# design.net
KiCad netlist of a schematic drawn in Altium Designer
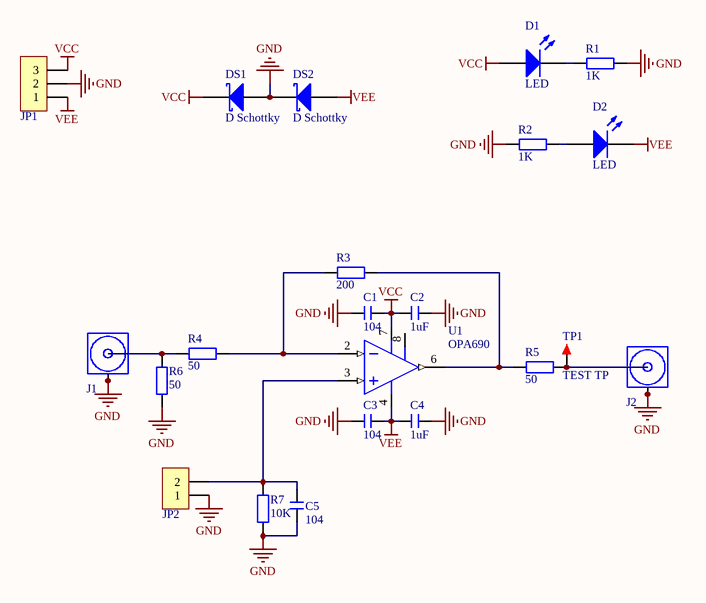
[diagram p0: 调偏电路.SchDoc]

(export (version "E")
  (design (tool "Eeschema 10.0.6"))
  (components
    (comp (ref "C1")
      (value "104")
      (footprint "C 0603")
      (description "无极性贴片电容")
      (fields (field (name "版权归属") "源创客"))
      (libsource (lib "电阻-电容-电感") (part "C"))
    )
    (comp (ref "C2")
      (value "1uF")
      (footprint "C 0603")
      (description "无极性贴片电容")
      (fields (field (name "版权归属") "源创客"))
      (libsource (lib "电阻-电容-电感") (part "C"))
    )
    (comp (ref "C3")
      (value "104")
      (footprint "C 0603")
      (description "无极性贴片电容")
      (fields (field (name "版权归属") "源创客"))
      (libsource (lib "电阻-电容-电感") (part "C"))
    )
    (comp (ref "C4")
      (value "1uF")
      (footprint "C 0603")
      (description "无极性贴片电容")
      (fields (field (name "版权归属") "源创客"))
      (libsource (lib "电阻-电容-电感") (part "C"))
    )
    (comp (ref "C5")
      (value "104")
      (footprint "C 0603")
      (description "无极性贴片电容")
      (fields (field (name "版权归属") "源创客"))
      (libsource (lib "电阻-电容-电感") (part "C"))
    )
    (comp (ref "D1")
      (value "LED")
      (footprint "LED_0805")
      (description "发光二极管")
      (fields (field (name "PUBLISHER") "Altium Limited"))
      (libsource (lib "LIB") (part "LED"))
    )
    (comp (ref "D2")
      (value "LED")
      (footprint "LED_0805")
      (description "发光二极管")
      (fields (field (name "PUBLISHER") "Altium Limited"))
      (libsource (lib "LIB") (part "LED"))
    )
    (comp (ref "DS1")
      (value "D Schottky")
      (footprint "DIODE-SMA")
      (description "Schottky Diode")
      (fields (field (name "PUBLISHER") "Altium Limited"))
      (libsource (lib "LIB") (part "D Schottky"))
    )
    (comp (ref "DS2")
      (value "D Schottky")
      (footprint "DIODE-SMA")
      (description "Schottky Diode")
      (fields (field (name "PUBLISHER") "Altium Limited"))
      (libsource (lib "LIB") (part "D Schottky"))
    )
    (comp (ref "J1") (value "COAX") (footprint "MCX5.08-5-H") (libsource (lib "LIB") (part "COAX")))
    (comp (ref "J2") (value "COAX") (footprint "MCX5.08-5-H") (libsource (lib "LIB") (part "COAX")))
    (comp (ref "JP1")
      (value "HDR-1X3")
      (footprint "XH2.54-3P_H")
      (description "3P接插件")
      (fields (field (name "版权归属") "源创客"))
      (libsource (lib "接插件") (part "Header 3"))
    )
    (comp (ref "JP2")
      (value "HDR-1X2")
      (footprint "HDR-1X2")
      (description "2P接插件")
      (fields (field (name "版权归属") "源创客"))
      (libsource (lib "接插件") (part "Header 2"))
    )
    (comp (ref "R1")
      (value "1K")
      (footprint "R 0805")
      (description "贴片电阻")
      (fields (field (name "版权归属") "源创客"))
      (libsource (lib "电阻-电容-电感") (part "R"))
    )
    (comp (ref "R2")
      (value "1K")
      (footprint "R 0805")
      (description "贴片电阻")
      (fields (field (name "版权归属") "源创客"))
      (libsource (lib "电阻-电容-电感") (part "R"))
    )
    (comp (ref "R3")
      (value "200")
      (footprint "R 0603")
      (description "贴片电阻")
      (fields (field (name "版权归属") "源创客"))
      (libsource (lib "电阻-电容-电感") (part "R"))
    )
    (comp (ref "R4")
      (value "50")
      (footprint "R 0603")
      (description "贴片电阻")
      (fields (field (name "版权归属") "源创客"))
      (libsource (lib "电阻-电容-电感") (part "R"))
    )
    (comp (ref "R5")
      (value "50")
      (footprint "R 0603")
      (description "贴片电阻")
      (fields (field (name "版权归属") "源创客"))
      (libsource (lib "电阻-电容-电感") (part "R"))
    )
    (comp (ref "R6")
      (value "50")
      (footprint "R 0603")
      (description "贴片电阻")
      (fields (field (name "版权归属") "源创客"))
      (libsource (lib "电阻-电容-电感") (part "R"))
    )
    (comp (ref "R7")
      (value "10K")
      (footprint "R 0603")
      (description "贴片电阻")
      (fields (field (name "版权归属") "源创客"))
      (libsource (lib "电阻-电容-电感") (part "R"))
    )
    (comp (ref "TP1")
      (value "TEST TP")
      (footprint "TEST TP1.4_B")
      (description "测试环")
      (fields (field (name "版权归属") "源创客"))
      (libsource (lib "未分类器件") (part "TEST TP"))
    )
    (comp (ref "U1")
      (value "OPA690")
      (footprint "LIB:SOIC8_N")
      (description "具有禁用功能的宽带电压反馈运算放大器")
      (libsource (lib "LIB") (part "OPA690ID"))
    )
  )
  (nets
    (net (code "1") (name "GND") (class "Default")
      (node (ref "C1") (pin "1") (pinfunction "1_1") (pintype "passive"))
      (node (ref "C2") (pin "2") (pinfunction "2_2") (pintype "passive"))
      (node (ref "C3") (pin "1") (pinfunction "1_1") (pintype "passive"))
      (node (ref "C4") (pin "2") (pinfunction "2_2") (pintype "passive"))
      (node (ref "C5") (pin "1") (pinfunction "1_1") (pintype "passive"))
      (node (ref "DS1") (pin "1") (pinfunction "1_1") (pintype "passive"))
      (node (ref "DS2") (pin "2") (pinfunction "2_2") (pintype "passive"))
      (node (ref "J1") (pin "2") (pinfunction "GND_2") (pintype "passive"))
      (node (ref "J1") (pin "3") (pinfunction "GND_3") (pintype "passive"))
      (node (ref "J1") (pin "4") (pinfunction "GND_4") (pintype "passive"))
      (node (ref "J1") (pin "5") (pinfunction "GND_5") (pintype "passive"))
      (node (ref "J2") (pin "2") (pinfunction "GND_2") (pintype "passive"))
      (node (ref "J2") (pin "3") (pinfunction "GND_3") (pintype "passive"))
      (node (ref "J2") (pin "4") (pinfunction "GND_4") (pintype "passive"))
      (node (ref "J2") (pin "5") (pinfunction "GND_5") (pintype "passive"))
      (node (ref "JP1") (pin "2") (pinfunction "2_2") (pintype "passive"))
      (node (ref "JP2") (pin "1") (pinfunction "1_1") (pintype "passive"))
      (node (ref "R1") (pin "2") (pinfunction "2_2") (pintype "passive"))
      (node (ref "R2") (pin "1") (pinfunction "1_1") (pintype "passive"))
      (node (ref "R6") (pin "1") (pinfunction "1_1") (pintype "passive"))
      (node (ref "R7") (pin "1") (pinfunction "1_1") (pintype "passive"))
    )
    (net (code "2") (name "Net-(D1-K)") (class "Default")
      (node (ref "D1") (pin "2") (pinfunction "K_2") (pintype "passive"))
      (node (ref "R1") (pin "1") (pinfunction "1_1") (pintype "passive"))
    )
    (net (code "3") (name "Net-(D2-A)") (class "Default")
      (node (ref "D2") (pin "1") (pinfunction "A_1") (pintype "passive"))
      (node (ref "R2") (pin "2") (pinfunction "2_2") (pintype "passive"))
    )
    (net (code "4") (name "Net-(J1-Signal)") (class "Default")
      (node (ref "J1") (pin "1") (pinfunction "Signal_1") (pintype "passive"))
      (node (ref "R4") (pin "1") (pinfunction "1_1") (pintype "passive"))
      (node (ref "R6") (pin "2") (pinfunction "2_2") (pintype "passive"))
    )
    (net (code "5") (name "Net-(J2-Signal)") (class "Default")
      (node (ref "J2") (pin "1") (pinfunction "Signal_1") (pintype "passive"))
      (node (ref "R5") (pin "2") (pinfunction "2_2") (pintype "passive"))
      (node (ref "TP1") (pin "1") (pinfunction "1_1") (pintype "passive"))
    )
    (net (code "6") (name "Net-(U1-IN+)") (class "Default")
      (node (ref "C5") (pin "2") (pinfunction "2_2") (pintype "passive"))
      (node (ref "JP2") (pin "2") (pinfunction "2_2") (pintype "passive"))
      (node (ref "R7") (pin "2") (pinfunction "2_2") (pintype "passive"))
      (node (ref "U1") (pin "3") (pinfunction "IN+_3") (pintype "input"))
    )
    (net (code "7") (name "Net-(U1-IN-)") (class "Default")
      (node (ref "R3") (pin "1") (pinfunction "1_1") (pintype "passive"))
      (node (ref "R4") (pin "2") (pinfunction "2_2") (pintype "passive"))
      (node (ref "U1") (pin "2") (pinfunction "IN-_2") (pintype "input"))
    )
    (net (code "8") (name "Net-(U1-OUT)") (class "Default")
      (node (ref "R3") (pin "2") (pinfunction "2_2") (pintype "passive"))
      (node (ref "R5") (pin "1") (pinfunction "1_1") (pintype "passive"))
      (node (ref "U1") (pin "6") (pinfunction "OUT_6") (pintype "output"))
    )
    (net (code "9") (name "VCC") (class "Default")
      (node (ref "C1") (pin "2") (pinfunction "2_2") (pintype "passive"))
      (node (ref "C2") (pin "1") (pinfunction "1_1") (pintype "passive"))
      (node (ref "D1") (pin "1") (pinfunction "A_1") (pintype "passive"))
      (node (ref "DS1") (pin "2") (pinfunction "2_2") (pintype "passive"))
      (node (ref "JP1") (pin "3") (pinfunction "3_3") (pintype "passive"))
      (node (ref "U1") (pin "7") (pinfunction "V+_7") (pintype "power_in"))
    )
    (net (code "10") (name "VEE") (class "Default")
      (node (ref "C3") (pin "2") (pinfunction "2_2") (pintype "passive"))
      (node (ref "C4") (pin "1") (pinfunction "1_1") (pintype "passive"))
      (node (ref "D2") (pin "2") (pinfunction "K_2") (pintype "passive"))
      (node (ref "DS2") (pin "1") (pinfunction "1_1") (pintype "passive"))
      (node (ref "JP1") (pin "1") (pinfunction "1_1") (pintype "passive"))
      (node (ref "U1") (pin "4") (pinfunction "V-_4") (pintype "power_in"))
    )
    (net (code "11") (name "unconnected-(U1-DIS-Pad8)") (class "Default")
      (node (ref "U1") (pin "8") (pinfunction "DIS_8") (pintype "passive"))
    )
  )
)
